# lpc11c14.net
KiCad netlist of a schematic drawn in Altium Designer
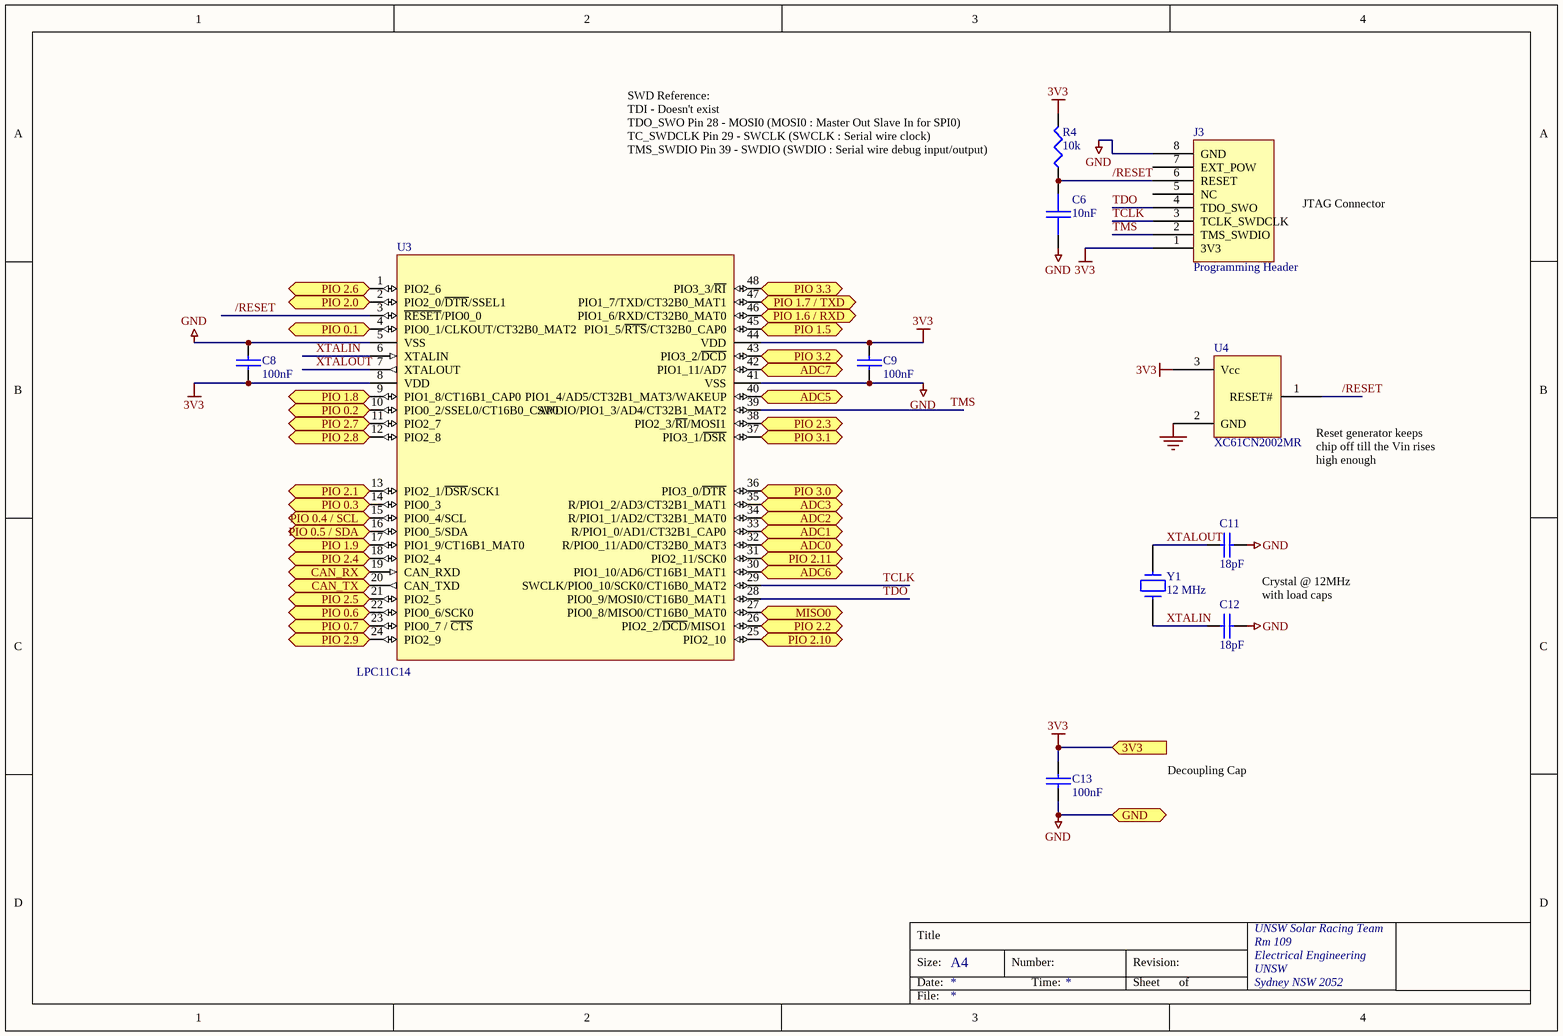
[diagram p0: lpc11c14.SchDoc]

(export (version "E")
  (design (tool "Eeschema 10.0.6"))
  (components
    (comp (ref "C6")
      (value "10nF")
      (footprint "0603")
      (description "Capacitor")
      (libsource (lib "SunswiftLib20030312RR") (part "CAP"))
    )
    (comp (ref "C8")
      (value "100nF")
      (footprint "0603")
      (description "Capacitor")
      (libsource (lib "*") (part "CAP"))
    )
    (comp (ref "C9")
      (value "100nF")
      (footprint "0603")
      (description "Capacitor")
      (libsource (lib "*") (part "CAP"))
    )
    (comp (ref "C11")
      (value "18pF")
      (footprint "0603")
      (description "Capacitor")
      (libsource (lib "*") (part "CAP"))
    )
    (comp (ref "C12")
      (value "18pF")
      (footprint "0603")
      (description "Capacitor")
      (libsource (lib "*") (part "CAP"))
    )
    (comp (ref "C13")
      (value "100nF")
      (footprint "0603")
      (description "Capacitor")
      (libsource (lib "*") (part "CAP"))
    )
    (comp (ref "J3")
      (value "Programming Header")
      (footprint "Footprint:IDC8")
      (description "LPC SWD Connector")
      (libsource (lib "2009_BatteryMaster") (part "LPCLink_Connector"))
    )
    (comp (ref "R4")
      (value "10k")
      (footprint "0603")
      (description "Resistor")
      (libsource (lib "SunswiftLib20030312RR") (part "RES1"))
    )
    (comp (ref "U3") (value "LPC11C14") (footprint "QFP48") (libsource (lib "LPC") (part "LPC11C14_Full")))
    (comp (ref "U4")
      (value "XC61CN2002MR")
      (footprint "SOT23-3")
      (description "SOT23 reset generator")
      (libsource (lib "*") (part "XC61F"))
    )
    (comp (ref "Y1")
      (value "12 MHz")
      (footprint "HC49/4H")
      (description "Crystal")
      (libsource (lib "*") (part "CRYSTAL"))
    )
  )
  (nets
    (net (code "1") (name "/ADC0") (class "Default")
      (node (ref "U3") (pin "32") (pinfunction "R/PIO0_11/AD0/CT32B0_MAT3_32") (pintype "bidirectional"))
    )
    (net (code "2") (name "/ADC1") (class "Default")
      (node (ref "U3") (pin "33") (pinfunction "R/PIO1_0/AD1/CT32B1_CAP0_33") (pintype "bidirectional"))
    )
    (net (code "3") (name "/ADC2") (class "Default")
      (node (ref "U3") (pin "34") (pinfunction "R/PIO1_1/AD2/CT32B1_MAT0_34") (pintype "bidirectional"))
    )
    (net (code "4") (name "/ADC3") (class "Default")
      (node (ref "U3") (pin "35") (pinfunction "R/PIO1_2/AD3/CT32B1_MAT1_35") (pintype "bidirectional"))
    )
    (net (code "5") (name "/ADC5") (class "Default")
      (node (ref "U3") (pin "40") (pinfunction "PIO1_4/AD5/CT32B1_MAT3/WAKEUP_40") (pintype "bidirectional"))
    )
    (net (code "6") (name "/ADC6") (class "Default")
      (node (ref "U3") (pin "30") (pinfunction "PIO1_10/AD6/CT16B1_MAT1_30") (pintype "bidirectional"))
    )
    (net (code "7") (name "/ADC7") (class "Default")
      (node (ref "U3") (pin "42") (pinfunction "PIO1_11/AD7_42") (pintype "bidirectional"))
    )
    (net (code "8") (name "/CAN_RX") (class "Default")
      (node (ref "U3") (pin "19") (pinfunction "CAN_RXD_19") (pintype "input"))
    )
    (net (code "9") (name "/CAN_TX") (class "Default")
      (node (ref "U3") (pin "20") (pinfunction "CAN_TXD_20") (pintype "output"))
    )
    (net (code "10") (name "/MISO0") (class "Default")
      (node (ref "U3") (pin "27") (pinfunction "PIO0_8/MISO0/CT16B0_MAT0_27") (pintype "bidirectional"))
    )
    (net (code "11") (name "/PIO 0.1") (class "Default")
      (node (ref "U3") (pin "4") (pinfunction "PIO0_1/CLKOUT/CT32B0_MAT2_4") (pintype "bidirectional"))
    )
    (net (code "12") (name "/PIO 0.2") (class "Default")
      (node (ref "U3") (pin "10") (pinfunction "PIO0_2/SSEL0/CT16B0_CAP0_10") (pintype "bidirectional"))
    )
    (net (code "13") (name "/PIO 0.3") (class "Default")
      (node (ref "U3") (pin "14") (pinfunction "PIO0_3_14") (pintype "bidirectional"))
    )
    (net (code "14") (name "/PIO 0.4 {slash} SCL") (class "Default")
      (node (ref "U3") (pin "15") (pinfunction "PIO0_4/SCL_15") (pintype "bidirectional"))
    )
    (net (code "15") (name "/PIO 0.5 {slash} SDA") (class "Default")
      (node (ref "U3") (pin "16") (pinfunction "PIO0_5/SDA_16") (pintype "bidirectional"))
    )
    (net (code "16") (name "/PIO 0.6") (class "Default")
      (node (ref "U3") (pin "22") (pinfunction "PIO0_6/SCK0_22") (pintype "bidirectional"))
    )
    (net (code "17") (name "/PIO 0.7") (class "Default")
      (node (ref "U3") (pin "23") (pinfunction "PIO0_7_/_~{CTS}_23") (pintype "bidirectional"))
    )
    (net (code "18") (name "/PIO 1.5") (class "Default")
      (node (ref "U3") (pin "45") (pinfunction "PIO1_5/~{RTS}/CT32B0_CAP0_45") (pintype "bidirectional"))
    )
    (net (code "19") (name "/PIO 1.6 {slash} RXD") (class "Default")
      (node (ref "U3") (pin "46") (pinfunction "PIO1_6/RXD/CT32B0_MAT0_46") (pintype "bidirectional"))
    )
    (net (code "20") (name "/PIO 1.7 {slash} TXD") (class "Default")
      (node (ref "U3") (pin "47") (pinfunction "PIO1_7/TXD/CT32B0_MAT1_47") (pintype "bidirectional"))
    )
    (net (code "21") (name "/PIO 1.8") (class "Default")
      (node (ref "U3") (pin "9") (pinfunction "PIO1_8/CT16B1_CAP0_9") (pintype "bidirectional"))
    )
    (net (code "22") (name "/PIO 1.9") (class "Default")
      (node (ref "U3") (pin "17") (pinfunction "PIO1_9/CT16B1_MAT0_17") (pintype "bidirectional"))
    )
    (net (code "23") (name "/PIO 2.0") (class "Default")
      (node (ref "U3") (pin "2") (pinfunction "PIO2_0/~{DTR}/SSEL1_2") (pintype "bidirectional"))
    )
    (net (code "24") (name "/PIO 2.1") (class "Default")
      (node (ref "U3") (pin "13") (pinfunction "PIO2_1/~{DSR}/SCK1_13") (pintype "bidirectional"))
    )
    (net (code "25") (name "/PIO 2.2") (class "Default")
      (node (ref "U3") (pin "26") (pinfunction "PIO2_2/~{DCD}/MISO1_26") (pintype "bidirectional"))
    )
    (net (code "26") (name "/PIO 2.3") (class "Default")
      (node (ref "U3") (pin "38") (pinfunction "PIO2_3/~{RI}/MOSI1_38") (pintype "bidirectional"))
    )
    (net (code "27") (name "/PIO 2.4") (class "Default")
      (node (ref "U3") (pin "18") (pinfunction "PIO2_4_18") (pintype "bidirectional"))
    )
    (net (code "28") (name "/PIO 2.5") (class "Default")
      (node (ref "U3") (pin "21") (pinfunction "PIO2_5_21") (pintype "bidirectional"))
    )
    (net (code "29") (name "/PIO 2.6") (class "Default")
      (node (ref "U3") (pin "1") (pinfunction "PIO2_6_1") (pintype "bidirectional"))
    )
    (net (code "30") (name "/PIO 2.7") (class "Default")
      (node (ref "U3") (pin "11") (pinfunction "PIO2_7_11") (pintype "bidirectional"))
    )
    (net (code "31") (name "/PIO 2.8") (class "Default")
      (node (ref "U3") (pin "12") (pinfunction "PIO2_8_12") (pintype "bidirectional"))
    )
    (net (code "32") (name "/PIO 2.9") (class "Default")
      (node (ref "U3") (pin "24") (pinfunction "PIO2_9_24") (pintype "bidirectional"))
    )
    (net (code "33") (name "/PIO 2.10") (class "Default")
      (node (ref "U3") (pin "25") (pinfunction "PIO2_10_25") (pintype "bidirectional"))
    )
    (net (code "34") (name "/PIO 2.11") (class "Default")
      (node (ref "U3") (pin "31") (pinfunction "PIO2_11/SCK0_31") (pintype "bidirectional"))
    )
    (net (code "35") (name "/PIO 3.0") (class "Default")
      (node (ref "U3") (pin "36") (pinfunction "PIO3_0/~{DTR}_36") (pintype "bidirectional"))
    )
    (net (code "36") (name "/PIO 3.1") (class "Default")
      (node (ref "U3") (pin "37") (pinfunction "PIO3_1/~{DSR}_37") (pintype "bidirectional"))
    )
    (net (code "37") (name "/PIO 3.2") (class "Default")
      (node (ref "U3") (pin "43") (pinfunction "PIO3_2/~{DCD}_43") (pintype "bidirectional"))
    )
    (net (code "38") (name "/PIO 3.3") (class "Default")
      (node (ref "U3") (pin "48") (pinfunction "PIO3_3/~{RI}_48") (pintype "bidirectional"))
    )
    (net (code "39") (name "/TCLK") (class "Default")
      (node (ref "J3") (pin "3") (pinfunction "TCLK_SWDCLK_3") (pintype "passive"))
      (node (ref "U3") (pin "29") (pinfunction "SWCLK/PIO0_10/SCK0/CT16B0_MAT2_29") (pintype "bidirectional"))
    )
    (net (code "40") (name "/TDO") (class "Default")
      (node (ref "J3") (pin "4") (pinfunction "TDO_SWO_4") (pintype "passive"))
      (node (ref "U3") (pin "28") (pinfunction "PIO0_9/MOSI0/CT16B0_MAT1_28") (pintype "bidirectional"))
    )
    (net (code "41") (name "/TMS") (class "Default")
      (node (ref "J3") (pin "2") (pinfunction "TMS_SWDIO_2") (pintype "passive"))
      (node (ref "U3") (pin "39") (pinfunction "SWDIO/PIO1_3/AD4/CT32B1_MAT2_39") (pintype "bidirectional"))
    )
    (net (code "42") (name "/XTALIN") (class "Default")
      (node (ref "C12") (pin "1") (pinfunction "1_1") (pintype "passive"))
      (node (ref "U3") (pin "6") (pinfunction "XTALIN_6") (pintype "input"))
      (node (ref "Y1") (pin "1") (pinfunction "1_1") (pintype "passive"))
    )
    (net (code "43") (name "/XTALOUT") (class "Default")
      (node (ref "C11") (pin "1") (pinfunction "1_1") (pintype "passive"))
      (node (ref "U3") (pin "7") (pinfunction "XTALOUT_7") (pintype "output"))
      (node (ref "Y1") (pin "2") (pinfunction "2_2") (pintype "passive"))
    )
    (net (code "44") (name "/{slash}RESET") (class "Default")
      (node (ref "C6") (pin "1") (pinfunction "1_1") (pintype "passive"))
      (node (ref "J3") (pin "6") (pinfunction "RESET_6") (pintype "passive"))
      (node (ref "R4") (pin "1") (pinfunction "1_1") (pintype "passive"))
      (node (ref "U3") (pin "3") (pinfunction "~{RESET}/PIO0_0_3") (pintype "bidirectional"))
      (node (ref "U4") (pin "1") (pinfunction "RESET#_1") (pintype "passive"))
    )
    (net (code "45") (name "3V3") (class "Default")
      (node (ref "C13") (pin "1") (pinfunction "1_1") (pintype "passive"))
      (node (ref "C8") (pin "2") (pinfunction "2_2") (pintype "passive"))
      (node (ref "C9") (pin "1") (pinfunction "1_1") (pintype "passive"))
      (node (ref "J3") (pin "1") (pinfunction "3V3_1") (pintype "passive"))
      (node (ref "R4") (pin "2") (pinfunction "2_2") (pintype "passive"))
      (node (ref "U3") (pin "44") (pinfunction "VDD_44") (pintype "power_in"))
      (node (ref "U3") (pin "8") (pinfunction "VDD_8") (pintype "power_in"))
      (node (ref "U4") (pin "3") (pinfunction "Vcc_3") (pintype "passive"))
    )
    (net (code "46") (name "GND") (class "Default")
      (node (ref "C11") (pin "2") (pinfunction "2_2") (pintype "passive"))
      (node (ref "C12") (pin "2") (pinfunction "2_2") (pintype "passive"))
      (node (ref "C13") (pin "2") (pinfunction "2_2") (pintype "passive"))
      (node (ref "C6") (pin "2") (pinfunction "2_2") (pintype "passive"))
      (node (ref "C8") (pin "1") (pinfunction "1_1") (pintype "passive"))
      (node (ref "C9") (pin "2") (pinfunction "2_2") (pintype "passive"))
      (node (ref "J3") (pin "8") (pinfunction "GND_8") (pintype "passive"))
      (node (ref "U3") (pin "41") (pinfunction "VSS_41") (pintype "power_in"))
      (node (ref "U3") (pin "5") (pinfunction "VSS_5") (pintype "power_in"))
      (node (ref "U4") (pin "2") (pinfunction "GND_2") (pintype "passive"))
    )
    (net (code "47") (name "unconnected-(J3-EXT_POW-Pad7)") (class "Default")
      (node (ref "J3") (pin "7") (pinfunction "EXT_POW_7") (pintype "passive"))
    )
    (net (code "48") (name "unconnected-(J3-NC-Pad5)") (class "Default")
      (node (ref "J3") (pin "5") (pinfunction "NC_5") (pintype "passive"))
    )
  )
)
